# SparkFun_9DoF_ISM330DHCX-MMC5983MA_Qwiic.net
KiCad netlist of a schematic drawn in EAGLE
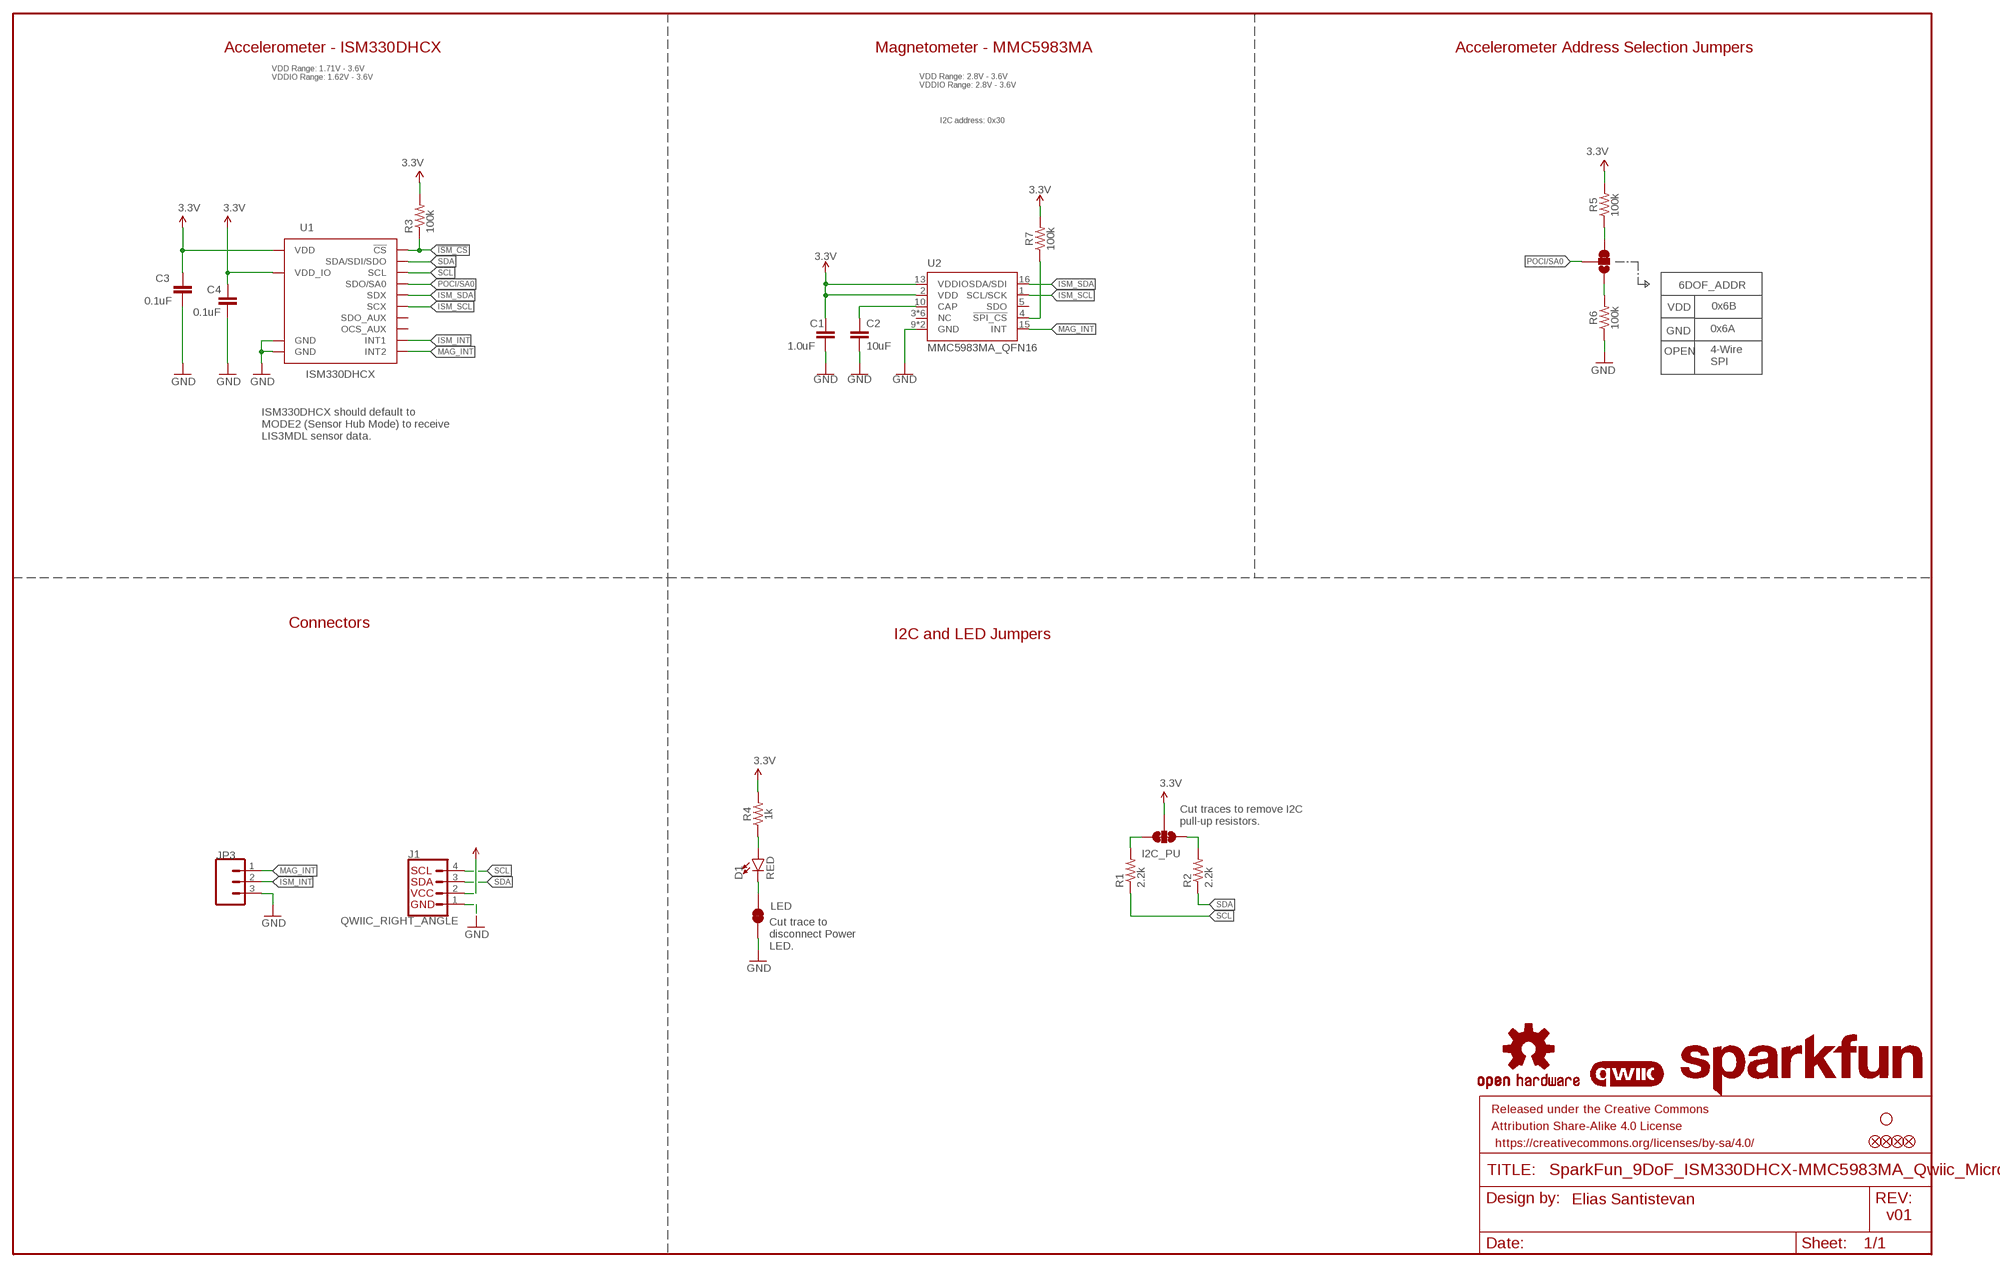
[diagram p0: schematic, sheet 1]

(export (version "E")
  (design (tool "Eeschema 10.0.6"))
  (components
    (comp (ref "6DOF_ADDR")
      (value "JUMPER-SMT_3_1-NC_TRACE_SILK")
      (footprint "eagle-import:SMT-JUMPER_3_1-NC_TRACE_SILK")
      (libsource (lib "eagle-import") (part "JUMPER-SMT_3_1-NC_TRACE_SILK"))
    )
    (comp (ref "C1")
      (value "1.0uF")
      (footprint "eagle-import:0402-TIGHT")
      (libsource (lib "eagle-import") (part "1.0UF-0402T-16V-10%"))
    )
    (comp (ref "C2")
      (value "10uF")
      (footprint "eagle-import:0402-TIGHT")
      (libsource (lib "eagle-import") (part "10UF-0402T-6.3V-20%"))
    )
    (comp (ref "C3")
      (value "0.1uF")
      (footprint "eagle-import:0402-TIGHT")
      (libsource (lib "eagle-import") (part "0.1UF-0402T-16V-10%"))
    )
    (comp (ref "C4")
      (value "0.1uF")
      (footprint "eagle-import:0402-TIGHT")
      (libsource (lib "eagle-import") (part "0.1UF-0402T-16V-10%"))
    )
    (comp (ref "D1")
      (value "RED")
      (footprint "eagle-import:0402-TIGHT")
      (libsource (lib "eagle-import") (part "LED_0402"))
    )
    (comp (ref "FD1")
      (value "FIDUCIALUFIDUCIAL")
      (footprint "eagle-import:FIDUCIAL-MICRO")
      (libsource (lib "eagle-import") (part "FIDUCIALUFIDUCIAL"))
    )
    (comp (ref "FD2")
      (value "FIDUCIALUFIDUCIAL")
      (footprint "eagle-import:FIDUCIAL-MICRO")
      (libsource (lib "eagle-import") (part "FIDUCIALUFIDUCIAL"))
    )
    (comp (ref "FID1")
      (value "FIDUCIALUFIDUCIAL")
      (footprint "eagle-import:FIDUCIAL-MICRO")
      (libsource (lib "eagle-import") (part "FIDUCIALUFIDUCIAL"))
    )
    (comp (ref "FID2")
      (value "FIDUCIALUFIDUCIAL")
      (footprint "eagle-import:FIDUCIAL-MICRO")
      (libsource (lib "eagle-import") (part "FIDUCIALUFIDUCIAL"))
    )
    (comp (ref "FRAME2")
      (value "FRAME-LEDGER")
      (footprint "eagle-import:CREATIVE_COMMONS")
      (libsource (lib "eagle-import") (part "FRAME-LEDGER"))
    )
    (comp (ref "I2C_PU")
      (value "S_MODE")
      (footprint "eagle-import:SMT-JUMPER_3_2-NC_TRACE_SILK")
      (libsource (lib "eagle-import") (part "JUMPER-SMT_3_2-NC_TRACE_SILK"))
    )
    (comp (ref "J1")
      (value "QWIIC_RIGHT_ANGLE")
      (footprint "eagle-import:JST04_1MM_RA")
      (libsource (lib "eagle-import") (part "QWIIC_CONNECTORJS-1MM"))
    )
    (comp (ref "JP3")
      (value "IO")
      (footprint "eagle-import:1X03_NO_SILK")
      (libsource (lib "eagle-import") (part "CONN_031X03_NO_SILK"))
    )
    (comp (ref "LED")
      (value "JUMPER-SMT_2_NC_TRACE_SILK")
      (footprint "eagle-import:SMT-JUMPER_2_NC_TRACE_SILK")
      (libsource (lib "eagle-import") (part "JUMPER-SMT_2_NC_TRACE_SILK"))
    )
    (comp (ref "LOGO1")
      (value "QWIIC_LOGO_4MM")
      (footprint "eagle-import:QWIIC_4MM")
      (libsource (lib "eagle-import") (part "QWIIC_LOGO_4MM"))
    )
    (comp (ref "LOGO2")
      (value "OSHW-LOGOMINI")
      (footprint "eagle-import:OSHW-LOGO-MINI")
      (libsource (lib "eagle-import") (part "OSHW-LOGOMINI"))
    )
    (comp (ref "LOGO3")
      (value "SFE_LOGO_NAMEBLANK")
      (footprint "eagle-import:BLANK")
      (libsource (lib "eagle-import") (part "SFE_LOGO_NAMEBLANK"))
    )
    (comp (ref "R1")
      (value "2.2k")
      (footprint "eagle-import:0402-TIGHT")
      (libsource (lib "eagle-import") (part "2.2KOHM-0402T-1/16W-1%"))
    )
    (comp (ref "R2")
      (value "2.2k")
      (footprint "eagle-import:0402-TIGHT")
      (libsource (lib "eagle-import") (part "2.2KOHM-0402T-1/16W-1%"))
    )
    (comp (ref "R3")
      (value "100k")
      (footprint "eagle-import:0402-TIGHT")
      (libsource (lib "eagle-import") (part "100KOHM-0402T-1/16W-1%"))
    )
    (comp (ref "R4")
      (value "1k")
      (footprint "eagle-import:0402-TIGHT")
      (libsource (lib "eagle-import") (part "1KOHM-0402T-1/16W-1%"))
    )
    (comp (ref "R5")
      (value "100k")
      (footprint "eagle-import:0402-TIGHT")
      (libsource (lib "eagle-import") (part "100KOHM-0402T-1/16W-1%"))
    )
    (comp (ref "R6")
      (value "100k")
      (footprint "eagle-import:0402-TIGHT")
      (libsource (lib "eagle-import") (part "100KOHM-0402T-1/16W-1%"))
    )
    (comp (ref "R7")
      (value "100k")
      (footprint "eagle-import:0402-TIGHT")
      (libsource (lib "eagle-import") (part "100KOHM-0402T-1/16W-1%"))
    )
    (comp (ref "STANDOFF2")
      (value "STAND-OFFTIGHT")
      (footprint "eagle-import:STAND-OFF-TIGHT")
      (libsource (lib "eagle-import") (part "STAND-OFFTIGHT"))
    )
    (comp (ref "U1")
      (value "ISM330DHCX")
      (footprint "eagle-import:LGA-14L")
      (libsource (lib "eagle-import") (part "ISM330DHCX"))
    )
    (comp (ref "U2")
      (value "MMC5983MA_QFN16")
      (footprint "eagle-import:LGA-16-3X3MM-4X4PINS")
      (libsource (lib "eagle-import") (part "MMC5983MA_QFN16"))
    )
  )
  (nets
    (net (code "1") (name "/~{ISM_CS}") (class "Default")
      (node (ref "R3") (pin "1") (pinfunction "1_1") (pintype "passive"))
      (node (ref "U1") (pin "P12") (pinfunction "~{CS}_P12") (pintype "bidirectional"))
    )
    (net (code "2") (name "3.3V") (class "Default")
      (node (ref "C1") (pin "1") (pinfunction "1_1") (pintype "passive"))
      (node (ref "C3") (pin "1") (pinfunction "1_1") (pintype "passive"))
      (node (ref "C4") (pin "1") (pinfunction "1_1") (pintype "passive"))
      (node (ref "I2C_PU") (pin "2") (pinfunction "2_2") (pintype "passive"))
      (node (ref "J1") (pin "2") (pinfunction "2_2") (pintype "power_in"))
      (node (ref "R3") (pin "2") (pinfunction "2_2") (pintype "passive"))
      (node (ref "R4") (pin "2") (pinfunction "2_2") (pintype "passive"))
      (node (ref "R5") (pin "2") (pinfunction "2_2") (pintype "passive"))
      (node (ref "R7") (pin "2") (pinfunction "2_2") (pintype "passive"))
      (node (ref "U1") (pin "P5") (pinfunction "VDD_IO_P5") (pintype "power_in"))
      (node (ref "U1") (pin "P8") (pinfunction "VDD_P8") (pintype "power_in"))
      (node (ref "U2") (pin "13") (pinfunction "VDDIO_13") (pintype "power_in"))
      (node (ref "U2") (pin "2") (pinfunction "VDD_2") (pintype "power_in"))
    )
    (net (code "3") (name "GND") (class "Default")
      (node (ref "C1") (pin "2") (pinfunction "2_2") (pintype "passive"))
      (node (ref "C2") (pin "2") (pinfunction "2_2") (pintype "passive"))
      (node (ref "C3") (pin "2") (pinfunction "2_2") (pintype "passive"))
      (node (ref "C4") (pin "2") (pinfunction "2_2") (pintype "passive"))
      (node (ref "J1") (pin "1") (pinfunction "1_1") (pintype "power_in"))
      (node (ref "JP3") (pin "3") (pinfunction "3_3") (pintype "passive"))
      (node (ref "LED") (pin "1") (pinfunction "1_1") (pintype "passive"))
      (node (ref "R6") (pin "1") (pinfunction "1_1") (pintype "passive"))
      (node (ref "U1") (pin "P6") (pinfunction "GND_P6") (pintype "power_in"))
      (node (ref "U1") (pin "P7") (pinfunction "GND_P7") (pintype "power_in"))
      (node (ref "U2") (pin "11") (pinfunction "GND_11") (pintype "power_in"))
      (node (ref "U2") (pin "9") (pinfunction "GND_9") (pintype "power_in"))
    )
    (net (code "4") (name "ISM_INT") (class "Default")
      (node (ref "JP3") (pin "2") (pinfunction "2_2") (pintype "passive"))
      (node (ref "U1") (pin "P4") (pinfunction "INT1_P4") (pintype "bidirectional"))
    )
    (net (code "5") (name "ISM_SCL") (class "Default")
      (node (ref "U1") (pin "P3") (pinfunction "SCX_P3") (pintype "bidirectional"))
      (node (ref "U2") (pin "1") (pinfunction "SCL/SCK_1") (pintype "bidirectional"))
    )
    (net (code "6") (name "ISM_SDA") (class "Default")
      (node (ref "U1") (pin "P2") (pinfunction "SDX_P2") (pintype "bidirectional"))
      (node (ref "U2") (pin "16") (pinfunction "SDA/SDI_16") (pintype "bidirectional"))
    )
    (net (code "7") (name "MAG_INT") (class "Default")
      (node (ref "JP3") (pin "1") (pinfunction "1_1") (pintype "passive"))
      (node (ref "U1") (pin "P9") (pinfunction "INT2_P9") (pintype "bidirectional"))
      (node (ref "U2") (pin "15") (pinfunction "INT_15") (pintype "output"))
    )
    (net (code "8") (name "Net-(6DOF_ADDR-Pad1)") (class "Default")
      (node (ref "6DOF_ADDR") (pin "1") (pinfunction "1_1") (pintype "passive"))
      (node (ref "R6") (pin "2") (pinfunction "2_2") (pintype "passive"))
    )
    (net (code "9") (name "Net-(6DOF_ADDR-Pad3)") (class "Default")
      (node (ref "6DOF_ADDR") (pin "3") (pinfunction "3_3") (pintype "passive"))
      (node (ref "R5") (pin "1") (pinfunction "1_1") (pintype "passive"))
    )
    (net (code "10") (name "Net-(D1-PadA)") (class "Default")
      (node (ref "D1") (pin "A") (pinfunction "A_A") (pintype "passive"))
      (node (ref "R4") (pin "1") (pinfunction "1_1") (pintype "passive"))
    )
    (net (code "11") (name "Net-(D1-PadC)") (class "Default")
      (node (ref "D1") (pin "C") (pinfunction "C_C") (pintype "passive"))
      (node (ref "LED") (pin "2") (pinfunction "2_2") (pintype "passive"))
    )
    (net (code "12") (name "Net-(I2C_PU-Pad1)") (class "Default")
      (node (ref "I2C_PU") (pin "1") (pinfunction "1_1") (pintype "passive"))
      (node (ref "R1") (pin "2") (pinfunction "2_2") (pintype "passive"))
    )
    (net (code "13") (name "Net-(I2C_PU-Pad3)") (class "Default")
      (node (ref "I2C_PU") (pin "3") (pinfunction "3_3") (pintype "passive"))
      (node (ref "R2") (pin "2") (pinfunction "2_2") (pintype "passive"))
    )
    (net (code "14") (name "Net-(U2-CAP)") (class "Default")
      (node (ref "C2") (pin "1") (pinfunction "1_1") (pintype "passive"))
      (node (ref "U2") (pin "10") (pinfunction "CAP_10") (pintype "passive"))
    )
    (net (code "15") (name "Net-(U2-~{SPI_CS})") (class "Default")
      (node (ref "R7") (pin "1") (pinfunction "1_1") (pintype "passive"))
      (node (ref "U2") (pin "4") (pinfunction "~{SPI_CS}_4") (pintype "input"))
    )
    (net (code "16") (name "POCI{slash}SA0") (class "Default")
      (node (ref "6DOF_ADDR") (pin "2") (pinfunction "2_2") (pintype "passive"))
      (node (ref "U1") (pin "P1") (pinfunction "SDO/SA0_P1") (pintype "bidirectional"))
    )
    (net (code "17") (name "SCL") (class "Default")
      (node (ref "J1") (pin "4") (pinfunction "4_4") (pintype "passive"))
      (node (ref "R1") (pin "1") (pinfunction "1_1") (pintype "passive"))
      (node (ref "U1") (pin "P13") (pinfunction "SCL_P13") (pintype "bidirectional"))
    )
    (net (code "18") (name "SDA") (class "Default")
      (node (ref "J1") (pin "3") (pinfunction "3_3") (pintype "passive"))
      (node (ref "R2") (pin "1") (pinfunction "1_1") (pintype "passive"))
      (node (ref "U1") (pin "P14") (pinfunction "SDA/SDI/SDO_P14") (pintype "bidirectional"))
    )
    (net (code "19") (name "unconnected-(U1-OCS_AUX-PadP10)") (class "Default")
      (node (ref "U1") (pin "P10") (pinfunction "OCS_AUX_P10") (pintype "bidirectional"))
    )
    (net (code "20") (name "unconnected-(U1-SDO_AUX-PadP11)") (class "Default")
      (node (ref "U1") (pin "P11") (pinfunction "SDO_AUX_P11") (pintype "bidirectional"))
    )
    (net (code "21") (name "unconnected-(U2-NC-Pad3)") (class "Default")
      (node (ref "U2") (pin "3") (pinfunction "NC_3") (pintype "no_connect"))
    )
    (net (code "22") (name "unconnected-(U2-NC-Pad6)") (class "Default")
      (node (ref "U2") (pin "6") (pinfunction "NC_6") (pintype "no_connect"))
    )
    (net (code "23") (name "unconnected-(U2-NC-Pad7)") (class "Default")
      (node (ref "U2") (pin "7") (pinfunction "NC_7") (pintype "no_connect"))
    )
    (net (code "24") (name "unconnected-(U2-NC-Pad8)") (class "Default")
      (node (ref "U2") (pin "8") (pinfunction "NC_8") (pintype "no_connect"))
    )
    (net (code "25") (name "unconnected-(U2-NC-Pad12)") (class "Default")
      (node (ref "U2") (pin "12") (pinfunction "NC_12") (pintype "no_connect"))
    )
    (net (code "26") (name "unconnected-(U2-NC-Pad14)") (class "Default")
      (node (ref "U2") (pin "14") (pinfunction "NC_14") (pintype "no_connect"))
    )
    (net (code "27") (name "unconnected-(U2-SDO-Pad5)") (class "Default")
      (node (ref "U2") (pin "5") (pinfunction "SDO_5") (pintype "output"))
    )
  )
)
